# Parasite.net
KiCad netlist of a schematic drawn in EAGLE
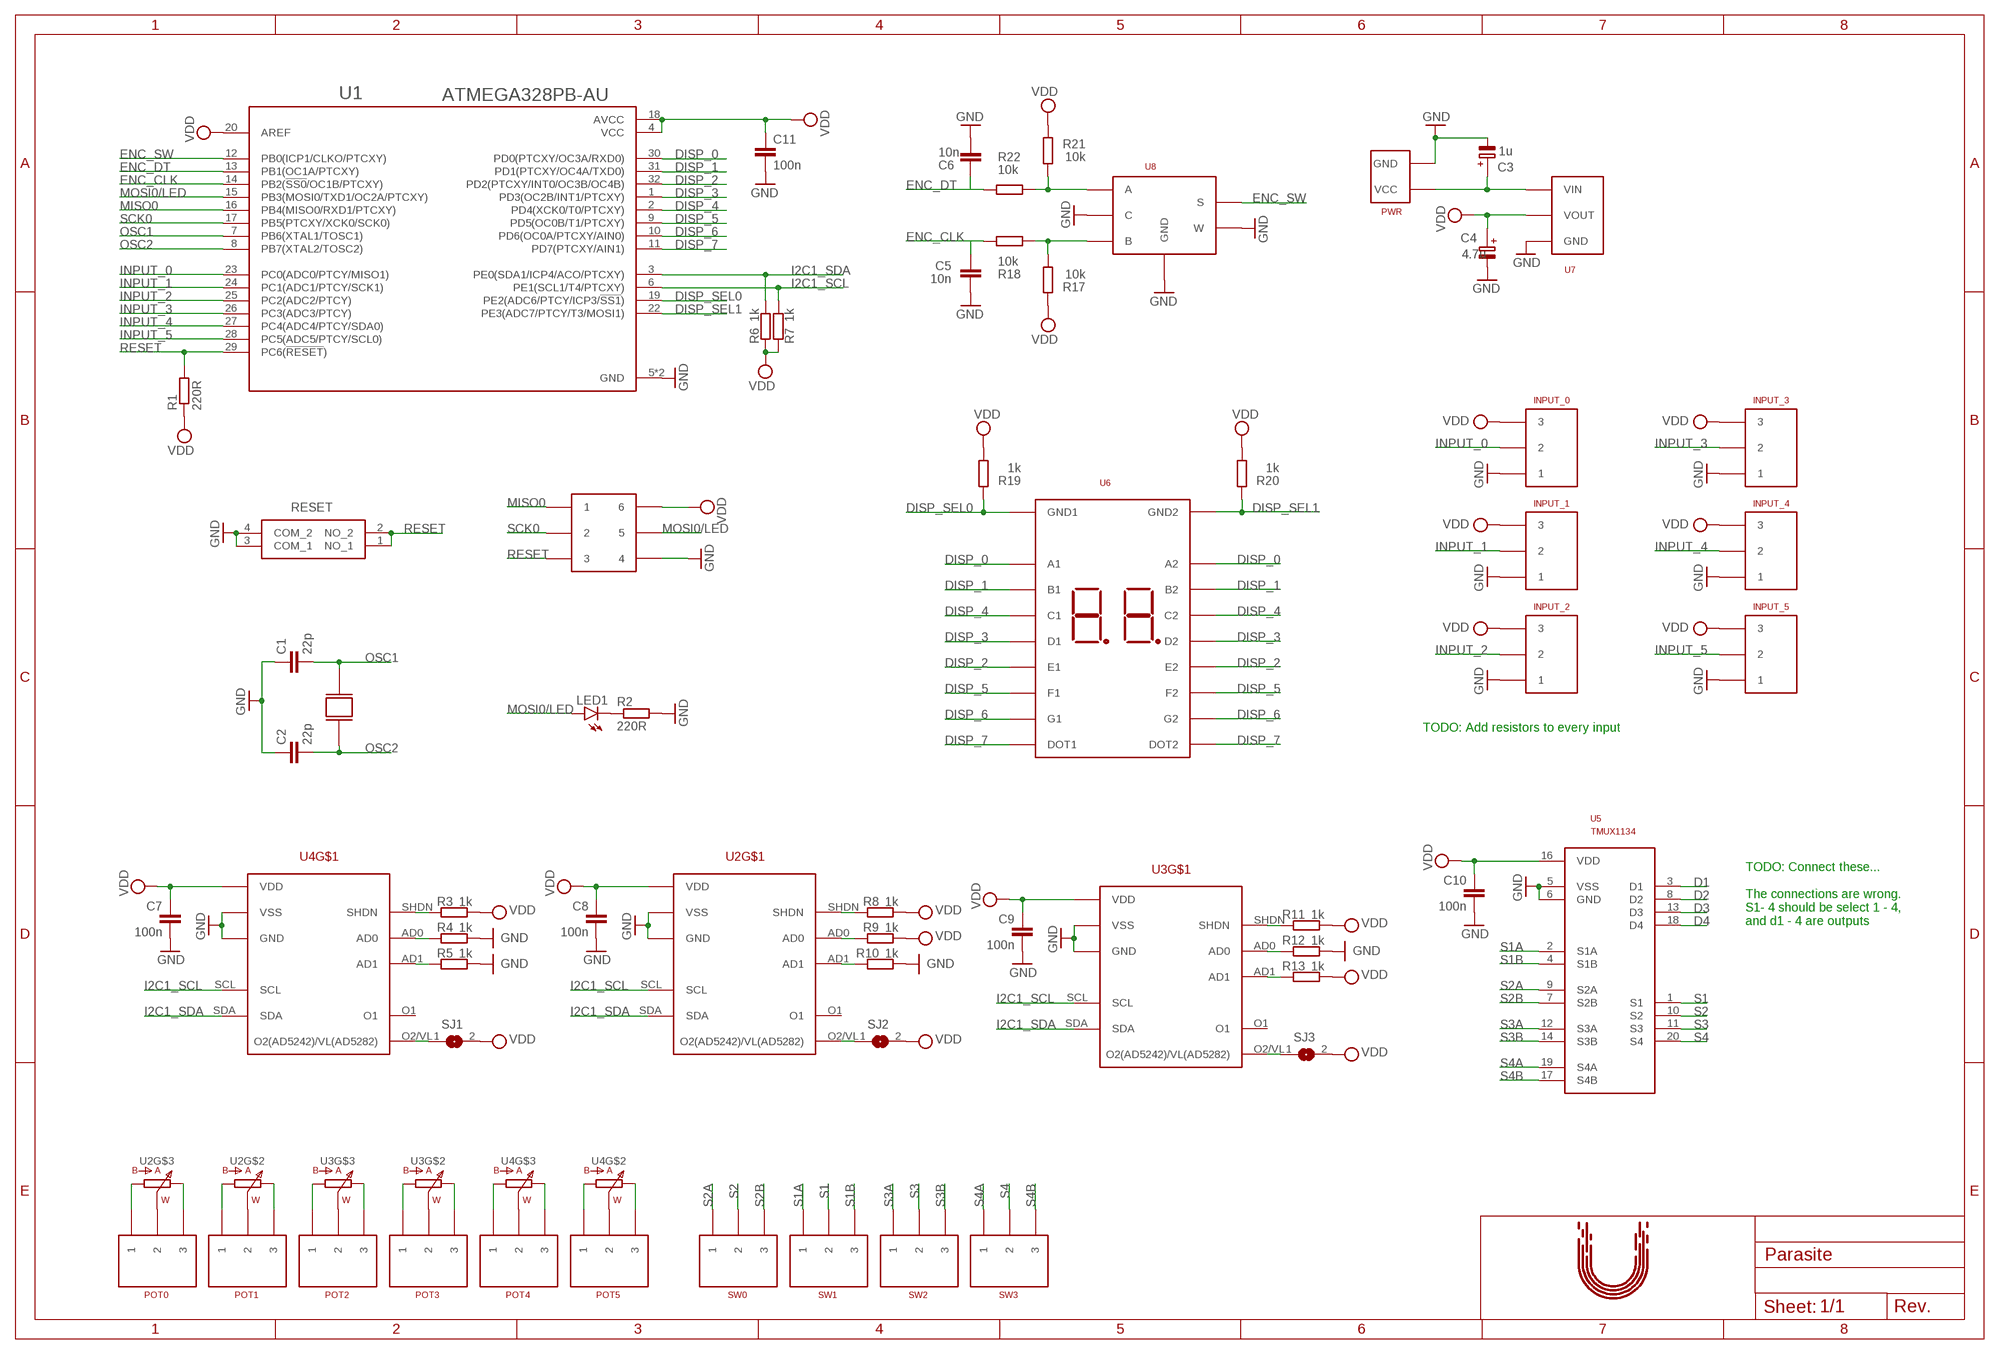
[diagram p0: schematic, sheet 1]

(export (version "E")
  (design (tool "Eeschema 10.0.6"))
  (components
    (comp (ref "C1")
      (value "22p")
      (footprint "eagle-import:C-1206")
      (libsource (lib "eagle-import") (part "CAPACITOR1206"))
    )
    (comp (ref "C2")
      (value "22p")
      (footprint "eagle-import:C-1206")
      (libsource (lib "eagle-import") (part "CAPACITOR1206"))
    )
    (comp (ref "C3")
      (value "1u")
      (footprint "eagle-import:UD-4X5,8_NICHICON")
      (libsource (lib "eagle-import") (part "ELECT_CAPACITORCAP6"))
    )
    (comp (ref "C4")
      (value "4.7u")
      (footprint "eagle-import:UD-4X5,8_NICHICON")
      (libsource (lib "eagle-import") (part "ELECT_CAPACITORCAP6"))
    )
    (comp (ref "C5")
      (value "10n")
      (footprint "eagle-import:C-1206")
      (libsource (lib "eagle-import") (part "CAPACITOR1206"))
    )
    (comp (ref "C6")
      (value "10n")
      (footprint "eagle-import:C-1206")
      (libsource (lib "eagle-import") (part "CAPACITOR1206"))
    )
    (comp (ref "C7")
      (value "100n")
      (footprint "eagle-import:C-1206")
      (libsource (lib "eagle-import") (part "CAPACITOR1206"))
    )
    (comp (ref "C8")
      (value "100n")
      (footprint "eagle-import:C-1206")
      (libsource (lib "eagle-import") (part "CAPACITOR1206"))
    )
    (comp (ref "C9")
      (value "100n")
      (footprint "eagle-import:C-1206")
      (libsource (lib "eagle-import") (part "CAPACITOR1206"))
    )
    (comp (ref "C10")
      (value "100n")
      (footprint "eagle-import:C-1206")
      (libsource (lib "eagle-import") (part "CAPACITOR1206"))
    )
    (comp (ref "C11")
      (value "100n")
      (footprint "eagle-import:C-1206")
      (libsource (lib "eagle-import") (part "CAPACITOR1206"))
    )
    (comp (ref "INPUT_0")
      (value "3_PIN_CONNECTOR")
      (footprint "eagle-import:3_PIN_CONNECTOR")
      (fields (field (name "MPN") " 22-23-2037"))
      (libsource (lib "eagle-import") (part "3_PIN_CONNECTOR"))
    )
    (comp (ref "INPUT_1")
      (value "3_PIN_CONNECTOR")
      (footprint "eagle-import:3_PIN_CONNECTOR")
      (fields (field (name "MPN") " 22-23-2037"))
      (libsource (lib "eagle-import") (part "3_PIN_CONNECTOR"))
    )
    (comp (ref "INPUT_2")
      (value "3_PIN_CONNECTOR")
      (footprint "eagle-import:3_PIN_CONNECTOR")
      (fields (field (name "MPN") " 22-23-2037"))
      (libsource (lib "eagle-import") (part "3_PIN_CONNECTOR"))
    )
    (comp (ref "INPUT_3")
      (value "3_PIN_CONNECTOR")
      (footprint "eagle-import:3_PIN_CONNECTOR")
      (fields (field (name "MPN") " 22-23-2037"))
      (libsource (lib "eagle-import") (part "3_PIN_CONNECTOR"))
    )
    (comp (ref "INPUT_4")
      (value "3_PIN_CONNECTOR")
      (footprint "eagle-import:3_PIN_CONNECTOR")
      (fields (field (name "MPN") " 22-23-2037"))
      (libsource (lib "eagle-import") (part "3_PIN_CONNECTOR"))
    )
    (comp (ref "INPUT_5")
      (value "3_PIN_CONNECTOR")
      (footprint "eagle-import:3_PIN_CONNECTOR")
      (fields (field (name "MPN") " 22-23-2037"))
      (libsource (lib "eagle-import") (part "3_PIN_CONNECTOR"))
    )
    (comp (ref "LED1")
      (value "LEDLED_THROUGH")
      (footprint "eagle-import:LED3MM")
      (libsource (lib "eagle-import") (part "LEDLED_THROUGH"))
    )
    (comp (ref "POT0")
      (value "3_PIN_CONNECTOR")
      (footprint "eagle-import:3_PIN_CONNECTOR")
      (fields (field (name "MPN") " 22-23-2037"))
      (libsource (lib "eagle-import") (part "3_PIN_CONNECTOR"))
    )
    (comp (ref "POT1")
      (value "3_PIN_CONNECTOR")
      (footprint "eagle-import:3_PIN_CONNECTOR")
      (fields (field (name "MPN") " 22-23-2037"))
      (libsource (lib "eagle-import") (part "3_PIN_CONNECTOR"))
    )
    (comp (ref "POT2")
      (value "3_PIN_CONNECTOR")
      (footprint "eagle-import:3_PIN_CONNECTOR")
      (fields (field (name "MPN") " 22-23-2037"))
      (libsource (lib "eagle-import") (part "3_PIN_CONNECTOR"))
    )
    (comp (ref "POT3")
      (value "3_PIN_CONNECTOR")
      (footprint "eagle-import:3_PIN_CONNECTOR")
      (fields (field (name "MPN") " 22-23-2037"))
      (libsource (lib "eagle-import") (part "3_PIN_CONNECTOR"))
    )
    (comp (ref "POT4")
      (value "3_PIN_CONNECTOR")
      (footprint "eagle-import:3_PIN_CONNECTOR")
      (fields (field (name "MPN") " 22-23-2037"))
      (libsource (lib "eagle-import") (part "3_PIN_CONNECTOR"))
    )
    (comp (ref "POT5")
      (value "3_PIN_CONNECTOR")
      (footprint "eagle-import:3_PIN_CONNECTOR")
      (fields (field (name "MPN") " 22-23-2037"))
      (libsource (lib "eagle-import") (part "3_PIN_CONNECTOR"))
    )
    (comp (ref "PWR")
      (value "PWR")
      (footprint "eagle-import:PWR")
      (libsource (lib "eagle-import") (part "PWR"))
    )
    (comp (ref "R1")
      (value "220R")
      (footprint "eagle-import:R1206")
      (libsource (lib "eagle-import") (part "RESISTOR1206"))
    )
    (comp (ref "R2")
      (value "220R")
      (footprint "eagle-import:R1206")
      (libsource (lib "eagle-import") (part "RESISTOR1206"))
    )
    (comp (ref "R3")
      (value "1k")
      (footprint "eagle-import:R1206")
      (libsource (lib "eagle-import") (part "RESISTOR1206"))
    )
    (comp (ref "R4")
      (value "1k")
      (footprint "eagle-import:R1206")
      (libsource (lib "eagle-import") (part "RESISTOR1206"))
    )
    (comp (ref "R5")
      (value "1k")
      (footprint "eagle-import:R1206")
      (libsource (lib "eagle-import") (part "RESISTOR1206"))
    )
    (comp (ref "R6")
      (value "1k")
      (footprint "eagle-import:R1206")
      (libsource (lib "eagle-import") (part "RESISTOR1206"))
    )
    (comp (ref "R7")
      (value "1k")
      (footprint "eagle-import:R1206")
      (libsource (lib "eagle-import") (part "RESISTOR1206"))
    )
    (comp (ref "R8")
      (value "1k")
      (footprint "eagle-import:R1206")
      (libsource (lib "eagle-import") (part "RESISTOR1206"))
    )
    (comp (ref "R9")
      (value "1k")
      (footprint "eagle-import:R1206")
      (libsource (lib "eagle-import") (part "RESISTOR1206"))
    )
    (comp (ref "R10")
      (value "1k")
      (footprint "eagle-import:R1206")
      (libsource (lib "eagle-import") (part "RESISTOR1206"))
    )
    (comp (ref "R11")
      (value "1k")
      (footprint "eagle-import:R1206")
      (libsource (lib "eagle-import") (part "RESISTOR1206"))
    )
    (comp (ref "R12")
      (value "1k")
      (footprint "eagle-import:R1206")
      (libsource (lib "eagle-import") (part "RESISTOR1206"))
    )
    (comp (ref "R13")
      (value "1k")
      (footprint "eagle-import:R1206")
      (libsource (lib "eagle-import") (part "RESISTOR1206"))
    )
    (comp (ref "R17")
      (value "10k")
      (footprint "eagle-import:R1206")
      (libsource (lib "eagle-import") (part "RESISTOR1206"))
    )
    (comp (ref "R18")
      (value "10k")
      (footprint "eagle-import:R1206")
      (libsource (lib "eagle-import") (part "RESISTOR1206"))
    )
    (comp (ref "R19")
      (value "1k")
      (footprint "eagle-import:R1206")
      (libsource (lib "eagle-import") (part "RESISTOR1206"))
    )
    (comp (ref "R20")
      (value "1k")
      (footprint "eagle-import:R1206")
      (libsource (lib "eagle-import") (part "RESISTOR1206"))
    )
    (comp (ref "R21")
      (value "10k")
      (footprint "eagle-import:R1206")
      (libsource (lib "eagle-import") (part "RESISTOR1206"))
    )
    (comp (ref "R22")
      (value "10k")
      (footprint "eagle-import:R1206")
      (libsource (lib "eagle-import") (part "RESISTOR1206"))
    )
    (comp (ref "RESET")
      (value "BUTTON")
      (footprint "eagle-import:PTS647SK38SMTR2LFS")
      (fields (field (name "MPN") "PTS647SK50SMTR2LFS"))
      (libsource (lib "eagle-import") (part "BUTTON"))
    )
    (comp (ref "SJ1")
      (value "JUMPER")
      (footprint "eagle-import:SJ")
      (libsource (lib "eagle-import") (part "JUMPER"))
    )
    (comp (ref "SJ2")
      (value "JUMPER")
      (footprint "eagle-import:SJ")
      (libsource (lib "eagle-import") (part "JUMPER"))
    )
    (comp (ref "SJ3")
      (value "JUMPER")
      (footprint "eagle-import:SJ")
      (libsource (lib "eagle-import") (part "JUMPER"))
    )
    (comp (ref "SW0")
      (value "3_PIN_CONNECTOR")
      (footprint "eagle-import:3_PIN_CONNECTOR")
      (fields (field (name "MPN") " 22-23-2037"))
      (libsource (lib "eagle-import") (part "3_PIN_CONNECTOR"))
    )
    (comp (ref "SW1")
      (value "3_PIN_CONNECTOR")
      (footprint "eagle-import:3_PIN_CONNECTOR")
      (fields (field (name "MPN") " 22-23-2037"))
      (libsource (lib "eagle-import") (part "3_PIN_CONNECTOR"))
    )
    (comp (ref "SW2")
      (value "3_PIN_CONNECTOR")
      (footprint "eagle-import:3_PIN_CONNECTOR")
      (fields (field (name "MPN") " 22-23-2037"))
      (libsource (lib "eagle-import") (part "3_PIN_CONNECTOR"))
    )
    (comp (ref "SW3")
      (value "3_PIN_CONNECTOR")
      (footprint "eagle-import:3_PIN_CONNECTOR")
      (fields (field (name "MPN") " 22-23-2037"))
      (libsource (lib "eagle-import") (part "3_PIN_CONNECTOR"))
    )
    (comp (ref "U$5")
      (value "UTBULT_DESIGN2")
      (footprint "eagle-import:UD_2")
      (libsource (lib "eagle-import") (part "UTBULT_DESIGN2"))
    )
    (comp (ref "U1")
      (value "ATMEGA328PB-AU")
      (footprint "eagle-import:QFP80P900X900X120-32N")
      (libsource (lib "eagle-import") (part "ATMEGA328PB-AU"))
    )
    (comp (ref "U2")
      (value "DIGITAL_POT_AD5242AD5242/AD5282")
      (footprint "eagle-import:SOP65P640X120-16N")
      (fields (field (name "MPN") "AD5242BRUZ1M"))
      (libsource (lib "eagle-import") (part "DIGITAL_POT_AD5242AD5242/AD5282"))
    )
    (comp (ref "U3")
      (value "DIGITAL_POT_AD5282AD5242/AD5282")
      (footprint "eagle-import:SOP65P640X120-16N")
      (fields (field (name "MPN") "AD5282BRUZ50"))
      (libsource (lib "eagle-import") (part "DIGITAL_POT_AD5282AD5242/AD5282"))
    )
    (comp (ref "U4")
      (value "DIGITAL_POT_AD5242AD5242/AD5282")
      (footprint "eagle-import:SOP65P640X120-16N")
      (fields (field (name "MPN") "AD5242BRUZ1M"))
      (libsource (lib "eagle-import") (part "DIGITAL_POT_AD5242AD5242/AD5282"))
    )
    (comp (ref "U5")
      (value "TMUX1134")
      (footprint "eagle-import:SOP65P640X120-20N")
      (fields (field (name "MPN") "TMUX1134PWR "))
      (libsource (lib "eagle-import") (part "TMUX1134"))
    )
    (comp (ref "U6")
      (value "7_SEGMENT_DISPLAY")
      (footprint "eagle-import:7_SEGMENT_DISPLAY")
      (fields (field (name "MPN") "LB-602MA2"))
      (libsource (lib "eagle-import") (part "7_SEGMENT_DISPLAY"))
    )
    (comp (ref "U7")
      (value "VOLTAGE_REGULATOR_LDL1117S50RVOLTAGE_REGULATOR_LDL1117S50R")
      (footprint "eagle-import:SOT230P700X180-4N")
      (fields (field (name "MPN") "LDL1117S50R"))
      (libsource (lib "eagle-import") (part "VOLTAGE_REGULATOR_LDL1117S50RVOLTAGE_REGULATOR_LDL1117S50R"))
    )
    (comp (ref "U8")
      (value "ROTARY_ENCODER")
      (footprint "eagle-import:ENCODER_PEC11H-4220F")
      (fields (field (name "MPN") "PEC11H-4220F-S0024"))
      (libsource (lib "eagle-import") (part "ROTARY_ENCODER"))
    )
    (comp (ref "U9")
      (value "3X2_PINHEADER3X2_PINHEADER")
      (footprint "eagle-import:HDRV6W64P254_2X3_900X508X838B")
      (fields (field (name "MPN") "5-146258-3"))
      (libsource (lib "eagle-import") (part "3X2_PINHEADER3X2_PINHEADER"))
    )
    (comp (ref "U10")
      (value "CRYSTAL_LFXTAL027946BULKCRYSTAL_LFXTAL027946BULK")
      (footprint "eagle-import:XTAL1140X490X430N")
      (fields (field (name "MPN") "LFXTAL027946Bulk"))
      (libsource (lib "eagle-import") (part "CRYSTAL_LFXTAL027946BULKCRYSTAL_LFXTAL027946BULK"))
    )
  )
  (nets
    (net (code "1") (name "/D1") (class "Default")
      (node (ref "U5") (pin "3") (pinfunction "D1_3") (pintype "bidirectional"))
    )
    (net (code "2") (name "/D2") (class "Default")
      (node (ref "U5") (pin "8") (pinfunction "D2_8") (pintype "bidirectional"))
    )
    (net (code "3") (name "/D3") (class "Default")
      (node (ref "U5") (pin "13") (pinfunction "D3_13") (pintype "bidirectional"))
    )
    (net (code "4") (name "/D4") (class "Default")
      (node (ref "U5") (pin "18") (pinfunction "D4_18") (pintype "bidirectional"))
    )
    (net (code "5") (name "/DISP_0") (class "Default")
      (node (ref "U1") (pin "30") (pinfunction "PD0(PTCXY/OC3A/RXD0)_30") (pintype "bidirectional"))
      (node (ref "U6") (pin "A1") (pinfunction "A1_A1") (pintype "input"))
      (node (ref "U6") (pin "A2") (pinfunction "A2_A2") (pintype "input"))
    )
    (net (code "6") (name "/DISP_1") (class "Default")
      (node (ref "U1") (pin "31") (pinfunction "PD1(PTCXY/OC4A/TXD0)_31") (pintype "bidirectional"))
      (node (ref "U6") (pin "B1") (pinfunction "B1_B1") (pintype "input"))
      (node (ref "U6") (pin "B2") (pinfunction "B2_B2") (pintype "input"))
    )
    (net (code "7") (name "/DISP_2") (class "Default")
      (node (ref "U1") (pin "32") (pinfunction "PD2(PTCXY/INT0/OC3B/OC4B)_32") (pintype "bidirectional"))
      (node (ref "U6") (pin "E1") (pinfunction "E1_E1") (pintype "input"))
      (node (ref "U6") (pin "E2") (pinfunction "E2_E2") (pintype "input"))
    )
    (net (code "8") (name "/DISP_3") (class "Default")
      (node (ref "U1") (pin "1") (pinfunction "PD3(OC2B/INT1/PTCXY)_1") (pintype "bidirectional"))
      (node (ref "U6") (pin "D1") (pinfunction "D1_D1") (pintype "input"))
      (node (ref "U6") (pin "D2") (pinfunction "D2_D2") (pintype "input"))
    )
    (net (code "9") (name "/DISP_4") (class "Default")
      (node (ref "U1") (pin "2") (pinfunction "PD4(XCK0/T0/PTCXY)_2") (pintype "bidirectional"))
      (node (ref "U6") (pin "C1") (pinfunction "C1_C1") (pintype "input"))
      (node (ref "U6") (pin "C2") (pinfunction "C2_C2") (pintype "input"))
    )
    (net (code "10") (name "/DISP_5") (class "Default")
      (node (ref "U1") (pin "9") (pinfunction "PD5(OC0B/T1/PTCXY)_9") (pintype "bidirectional"))
      (node (ref "U6") (pin "F1") (pinfunction "F1_F1") (pintype "input"))
      (node (ref "U6") (pin "F2") (pinfunction "F2_F2") (pintype "input"))
    )
    (net (code "11") (name "/DISP_6") (class "Default")
      (node (ref "U1") (pin "10") (pinfunction "PD6(OC0A/PTCXY/AIN0)_10") (pintype "bidirectional"))
      (node (ref "U6") (pin "G1") (pinfunction "G1_G1") (pintype "input"))
      (node (ref "U6") (pin "G2") (pinfunction "G2_G2") (pintype "input"))
    )
    (net (code "12") (name "/DISP_7") (class "Default")
      (node (ref "U1") (pin "11") (pinfunction "PD7(PTCXY/AIN1)_11") (pintype "bidirectional"))
      (node (ref "U6") (pin "DOT1") (pinfunction "DOT1_DOT1") (pintype "input"))
      (node (ref "U6") (pin "DOT2") (pinfunction "DOT2_DOT2") (pintype "input"))
    )
    (net (code "13") (name "/DISP_SEL0") (class "Default")
      (node (ref "R19") (pin "1") (pinfunction "1_1") (pintype "passive"))
      (node (ref "U1") (pin "19") (pinfunction "PE2(ADC6/PTCY/ICP3/~{SS1})_19") (pintype "bidirectional"))
      (node (ref "U6") (pin "GND1") (pinfunction "GND1_GND1") (pintype "output"))
    )
    (net (code "14") (name "/DISP_SEL1") (class "Default")
      (node (ref "R20") (pin "1") (pinfunction "1_1") (pintype "passive"))
      (node (ref "U1") (pin "22") (pinfunction "PE3(ADC7/PTCY/T3/MOSI1)_22") (pintype "bidirectional"))
      (node (ref "U6") (pin "GND2") (pinfunction "GND2_GND2") (pintype "output"))
    )
    (net (code "15") (name "/ENC_CLK") (class "Default")
      (node (ref "C5") (pin "P$2") (pinfunction "2_P$2") (pintype "passive"))
      (node (ref "R18") (pin "2") (pinfunction "2_2") (pintype "passive"))
      (node (ref "U1") (pin "14") (pinfunction "PB2(~{SS0}/OC1B/PTCXY)_14") (pintype "bidirectional"))
    )
    (net (code "16") (name "/ENC_DT") (class "Default")
      (node (ref "C6") (pin "P$2") (pinfunction "2_P$2") (pintype "passive"))
      (node (ref "R22") (pin "2") (pinfunction "2_2") (pintype "passive"))
      (node (ref "U1") (pin "13") (pinfunction "PB1(OC1A/PTCXY)_13") (pintype "bidirectional"))
    )
    (net (code "17") (name "/ENC_SW") (class "Default")
      (node (ref "U1") (pin "12") (pinfunction "PB0(ICP1/CLKO/PTCXY)_12") (pintype "bidirectional"))
      (node (ref "U8") (pin "S") (pinfunction "S_S") (pintype "bidirectional"))
    )
    (net (code "18") (name "/I2C1_SCL") (class "Default")
      (node (ref "R7") (pin "1") (pinfunction "1_1") (pintype "passive"))
      (node (ref "U1") (pin "6") (pinfunction "PE1(SCL1/T4/PTCXY)_6") (pintype "bidirectional"))
      (node (ref "U2") (pin "SCL") (pinfunction "SCL_SCL") (pintype "input"))
      (node (ref "U3") (pin "SCL") (pinfunction "SCL_SCL") (pintype "input"))
      (node (ref "U4") (pin "SCL") (pinfunction "SCL_SCL") (pintype "input"))
    )
    (net (code "19") (name "/I2C1_SDA") (class "Default")
      (node (ref "R6") (pin "1") (pinfunction "1_1") (pintype "passive"))
      (node (ref "U1") (pin "3") (pinfunction "PE0(SDA1/ICP4/ACO/PTCXY)_3") (pintype "bidirectional"))
      (node (ref "U2") (pin "SDA") (pinfunction "SDA_SDA") (pintype "bidirectional"))
      (node (ref "U3") (pin "SDA") (pinfunction "SDA_SDA") (pintype "bidirectional"))
      (node (ref "U4") (pin "SDA") (pinfunction "SDA_SDA") (pintype "bidirectional"))
    )
    (net (code "20") (name "/INPUT_0") (class "Default")
      (node (ref "INPUT_0") (pin "P$2") (pinfunction "2_P$2") (pintype "bidirectional"))
      (node (ref "U1") (pin "23") (pinfunction "PC0(ADC0/PTCY/MISO1)_23") (pintype "bidirectional"))
    )
    (net (code "21") (name "/INPUT_1") (class "Default")
      (node (ref "INPUT_1") (pin "P$2") (pinfunction "2_P$2") (pintype "bidirectional"))
      (node (ref "U1") (pin "24") (pinfunction "PC1(ADC1/PTCY/SCK1)_24") (pintype "bidirectional"))
    )
    (net (code "22") (name "/INPUT_2") (class "Default")
      (node (ref "INPUT_2") (pin "P$2") (pinfunction "2_P$2") (pintype "bidirectional"))
      (node (ref "U1") (pin "25") (pinfunction "PC2(ADC2/PTCY)_25") (pintype "bidirectional"))
    )
    (net (code "23") (name "/INPUT_3") (class "Default")
      (node (ref "INPUT_3") (pin "P$2") (pinfunction "2_P$2") (pintype "bidirectional"))
      (node (ref "U1") (pin "26") (pinfunction "PC3(ADC3/PTCY)_26") (pintype "bidirectional"))
    )
    (net (code "24") (name "/INPUT_4") (class "Default")
      (node (ref "INPUT_4") (pin "P$2") (pinfunction "2_P$2") (pintype "bidirectional"))
      (node (ref "U1") (pin "27") (pinfunction "PC4(ADC4/PTCY/SDA0)_27") (pintype "bidirectional"))
    )
    (net (code "25") (name "/INPUT_5") (class "Default")
      (node (ref "INPUT_5") (pin "P$2") (pinfunction "2_P$2") (pintype "bidirectional"))
      (node (ref "U1") (pin "28") (pinfunction "PC5(ADC5/PTCY/SCL0)_28") (pintype "bidirectional"))
    )
    (net (code "26") (name "/MISO0") (class "Default")
      (node (ref "U1") (pin "16") (pinfunction "PB4(MISO0/RXD1/PTCXY)_16") (pintype "bidirectional"))
      (node (ref "U9") (pin "1") (pinfunction "1_1") (pintype "bidirectional"))
    )
    (net (code "27") (name "/MOSI0{slash}LED") (class "Default")
      (node (ref "LED1") (pin "A") (pinfunction "A_A") (pintype "passive"))
      (node (ref "U1") (pin "15") (pinfunction "PB3(MOSI0/TXD1/OC2A/PTCXY)_15") (pintype "bidirectional"))
      (node (ref "U9") (pin "5") (pinfunction "5_5") (pintype "bidirectional"))
    )
    (net (code "28") (name "/OSC1") (class "Default")
      (node (ref "C1") (pin "P$2") (pinfunction "2_P$2") (pintype "passive"))
      (node (ref "U1") (pin "7") (pinfunction "PB6(XTAL1/TOSC1)_7") (pintype "bidirectional"))
      (node (ref "U10") (pin "2") (pinfunction "P$2_2") (pintype "bidirectional"))
    )
    (net (code "29") (name "/OSC2") (class "Default")
      (node (ref "C2") (pin "P$2") (pinfunction "2_P$2") (pintype "passive"))
      (node (ref "U1") (pin "8") (pinfunction "PB7(XTAL2/TOSC2)_8") (pintype "bidirectional"))
      (node (ref "U10") (pin "1") (pinfunction "P$1_1") (pintype "bidirectional"))
    )
    (net (code "30") (name "/RESET") (class "Default")
      (node (ref "R1") (pin "2") (pinfunction "2_2") (pintype "passive"))
      (node (ref "RESET") (pin "1") (pinfunction "NO_1_1") (pintype "bidirectional"))
      (node (ref "RESET") (pin "2") (pinfunction "NO_2_2") (pintype "bidirectional"))
      (node (ref "U1") (pin "29") (pinfunction "PC6(~{RESET})_29") (pintype "bidirectional"))
      (node (ref "U9") (pin "3") (pinfunction "3_3") (pintype "bidirectional"))
    )
    (net (code "31") (name "/S1") (class "Default")
      (node (ref "SW1") (pin "P$2") (pinfunction "2_P$2") (pintype "bidirectional"))
      (node (ref "U5") (pin "1") (pinfunction "S1_1") (pintype "bidirectional"))
    )
    (net (code "32") (name "/S1A") (class "Default")
      (node (ref "SW1") (pin "P$1") (pinfunction "1_P$1") (pintype "bidirectional"))
      (node (ref "U5") (pin "2") (pinfunction "S1A_2") (pintype "bidirectional"))
    )
    (net (code "33") (name "/S1B") (class "Default")
      (node (ref "SW1") (pin "P$3") (pinfunction "3_P$3") (pintype "bidirectional"))
      (node (ref "U5") (pin "4") (pinfunction "S1B_4") (pintype "bidirectional"))
    )
    (net (code "34") (name "/S2") (class "Default")
      (node (ref "SW0") (pin "P$2") (pinfunction "2_P$2") (pintype "bidirectional"))
      (node (ref "U5") (pin "10") (pinfunction "S2_10") (pintype "bidirectional"))
    )
    (net (code "35") (name "/S2A") (class "Default")
      (node (ref "SW0") (pin "P$1") (pinfunction "1_P$1") (pintype "bidirectional"))
      (node (ref "U5") (pin "9") (pinfunction "S2A_9") (pintype "bidirectional"))
    )
    (net (code "36") (name "/S2B") (class "Default")
      (node (ref "SW0") (pin "P$3") (pinfunction "3_P$3") (pintype "bidirectional"))
      (node (ref "U5") (pin "7") (pinfunction "S2B_7") (pintype "bidirectional"))
    )
    (net (code "37") (name "/S3") (class "Default")
      (node (ref "SW2") (pin "P$2") (pinfunction "2_P$2") (pintype "bidirectional"))
      (node (ref "U5") (pin "11") (pinfunction "S3_11") (pintype "bidirectional"))
    )
    (net (code "38") (name "/S3A") (class "Default")
      (node (ref "SW2") (pin "P$1") (pinfunction "1_P$1") (pintype "bidirectional"))
      (node (ref "U5") (pin "12") (pinfunction "S3A_12") (pintype "bidirectional"))
    )
    (net (code "39") (name "/S3B") (class "Default")
      (node (ref "SW2") (pin "P$3") (pinfunction "3_P$3") (pintype "bidirectional"))
      (node (ref "U5") (pin "14") (pinfunction "S3B_14") (pintype "bidirectional"))
    )
    (net (code "40") (name "/S4") (class "Default")
      (node (ref "SW3") (pin "P$2") (pinfunction "2_P$2") (pintype "bidirectional"))
      (node (ref "U5") (pin "20") (pinfunction "S4_20") (pintype "bidirectional"))
    )
    (net (code "41") (name "/S4A") (class "Default")
      (node (ref "SW3") (pin "P$1") (pinfunction "1_P$1") (pintype "bidirectional"))
      (node (ref "U5") (pin "19") (pinfunction "S4A_19") (pintype "bidirectional"))
    )
    (net (code "42") (name "/S4B") (class "Default")
      (node (ref "SW3") (pin "P$3") (pinfunction "3_P$3") (pintype "bidirectional"))
      (node (ref "U5") (pin "17") (pinfunction "S4B_17") (pintype "bidirectional"))
    )
    (net (code "43") (name "/SCK0") (class "Default")
      (node (ref "U1") (pin "17") (pinfunction "PB5(PTCXY/XCK0/SCK0)_17") (pintype "bidirectional"))
      (node (ref "U9") (pin "2") (pinfunction "2_2") (pintype "bidirectional"))
    )
    (net (code "44") (name "GND") (class "Default")
      (node (ref "C1") (pin "P$1") (pinfunction "1_P$1") (pintype "passive"))
      (node (ref "C10") (pin "P$2") (pinfunction "2_P$2") (pintype "passive"))
      (node (ref "C11") (pin "P$2") (pinfunction "2_P$2") (pintype "passive"))
      (node (ref "C2") (pin "P$1") (pinfunction "1_P$1") (pintype "passive"))
      (node (ref "C3") (pin "-") (pinfunction "-_-") (pintype "passive"))
      (node (ref "C4") (pin "-") (pinfunction "-_-") (pintype "passive"))
      (node (ref "C5") (pin "P$1") (pinfunction "1_P$1") (pintype "passive"))
      (node (ref "C6") (pin "P$1") (pinfunction "1_P$1") (pintype "passive"))
      (node (ref "C7") (pin "P$2") (pinfunction "2_P$2") (pintype "passive"))
      (node (ref "C8") (pin "P$2") (pinfunction "2_P$2") (pintype "passive"))
      (node (ref "C9") (pin "P$2") (pinfunction "2_P$2") (pintype "passive"))
      (node (ref "INPUT_0") (pin "P$1") (pinfunction "1_P$1") (pintype "bidirectional"))
      (node (ref "INPUT_1") (pin "P$1") (pinfunction "1_P$1") (pintype "bidirectional"))
      (node (ref "INPUT_2") (pin "P$1") (pinfunction "1_P$1") (pintype "bidirectional"))
      (node (ref "INPUT_3") (pin "P$1") (pinfunction "1_P$1") (pintype "bidirectional"))
      (node (ref "INPUT_4") (pin "P$1") (pinfunction "1_P$1") (pintype "bidirectional"))
      (node (ref "INPUT_5") (pin "P$1") (pinfunction "1_P$1") (pintype "bidirectional"))
      (node (ref "PWR") (pin "P$2") (pinfunction "GND_P$2") (pintype "bidirectional"))
      (node (ref "R10") (pin "1") (pinfunction "1_1") (pintype "passive"))
      (node (ref "R12") (pin "1") (pinfunction "1_1") (pintype "passive"))
      (node (ref "R2") (pin "2") (pinfunction "2_2") (pintype "passive"))
      (node (ref "R4") (pin "1") (pinfunction "1_1") (pintype "passive"))
      (node (ref "R5") (pin "1") (pinfunction "1_1") (pintype "passive"))
      (node (ref "RESET") (pin "3") (pinfunction "COM_1_3") (pintype "bidirectional"))
      (node (ref "RESET") (pin "4") (pinfunction "COM_2_4") (pintype "bidirectional"))
      (node (ref "U1") (pin "21") (pinfunction "GND_21") (pintype "power_in"))
      (node (ref "U1") (pin "5") (pinfunction "GND_5") (pintype "power_in"))
      (node (ref "U2") (pin "GND") (pinfunction "GND_GND") (pintype "power_in"))
      (node (ref "U2") (pin "VSS") (pinfunction "VSS_VSS") (pintype "power_in"))
      (node (ref "U3") (pin "GND") (pinfunction "GND_GND") (pintype "power_in"))
      (node (ref "U3") (pin "VSS") (pinfunction "VSS_VSS") (pintype "power_in"))
      (node (ref "U4") (pin "GND") (pinfunction "GND_GND") (pintype "power_in"))
      (node (ref "U4") (pin "VSS") (pinfunction "VSS_VSS") (pintype "power_in"))
      (node (ref "U5") (pin "5") (pinfunction "VSS_5") (pintype "bidirectional"))
      (node (ref "U5") (pin "6") (pinfunction "GND_6") (pintype "bidirectional"))
      (node (ref "U7") (pin "1") (pinfunction "GND_1") (pintype "power_in"))
      (node (ref "U8") (pin "C") (pinfunction "C_C") (pintype "output"))
      (node (ref "U8") (pin "GND1") (pinfunction "GND_GND1") (pintype "power_in"))
      (node (ref "U8") (pin "GND2") (pinfunction "GND_GND2") (pintype "power_in"))
      (node (ref "U8") (pin "W") (pinfunction "W_W") (pintype "bidirectional"))
      (node (ref "U9") (pin "4") (pinfunction "4_4") (pintype "bidirectional"))
    )
    (net (code "45") (name "Net-(LED1-C)") (class "Default")
      (node (ref "LED1") (pin "K") (pinfunction "C_K") (pintype "passive"))
      (node (ref "R2") (pin "1") (pinfunction "1_1") (pintype "passive"))
    )
    (net (code "46") (name "Net-(POT0-1)") (class "Default")
      (node (ref "POT0") (pin "P$1") (pinfunction "1_P$1") (pintype "bidirectional"))
      (node (ref "U2") (pin "B2") (pinfunction "B_B2") (pintype "passive"))
    )
    (net (code "47") (name "Net-(POT0-2)") (class "Default")
      (node (ref "POT0") (pin "P$2") (pinfunction "2_P$2") (pintype "bidirectional"))
      (node (ref "U2") (pin "W2") (pinfunction "W_W2") (pintype "passive"))
    )
    (net (code "48") (name "Net-(POT0-3)") (class "Default")
      (node (ref "POT0") (pin "P$3") (pinfunction "3_P$3") (pintype "bidirectional"))
      (node (ref "U2") (pin "A2") (pinfunction "A_A2") (pintype "passive"))
    )
    (net (code "49") (name "Net-(POT1-1)") (class "Default")
      (node (ref "POT1") (pin "P$1") (pinfunction "1_P$1") (pintype "bidirectional"))
      (node (ref "U2") (pin "B1") (pinfunction "B_B1") (pintype "passive"))
    )
    (net (code "50") (name "Net-(POT1-2)") (class "Default")
      (node (ref "POT1") (pin "P$2") (pinfunction "2_P$2") (pintype "bidirectional"))
      (node (ref "U2") (pin "W1") (pinfunction "W_W1") (pintype "passive"))
    )
    (net (code "51") (name "Net-(POT1-3)") (class "Default")
      (node (ref "POT1") (pin "P$3") (pinfunction "3_P$3") (pintype "bidirectional"))
      (node (ref "U2") (pin "A1") (pinfunction "A_A1") (pintype "passive"))
    )
    (net (code "52") (name "Net-(POT2-1)") (class "Default")
      (node (ref "POT2") (pin "P$1") (pinfunction "1_P$1") (pintype "bidirectional"))
      (node (ref "U3") (pin "B2") (pinfunction "B_B2") (pintype "passive"))
    )
    (net (code "53") (name "Net-(POT2-2)") (class "Default")
      (node (ref "POT2") (pin "P$2") (pinfunction "2_P$2") (pintype "bidirectional"))
      (node (ref "U3") (pin "W2") (pinfunction "W_W2") (pintype "passive"))
    )
    (net (code "54") (name "Net-(POT2-3)") (class "Default")
      (node (ref "POT2") (pin "P$3") (pinfunction "3_P$3") (pintype "bidirectional"))
      (node (ref "U3") (pin "A2") (pinfunction "A_A2") (pintype "passive"))
    )
    (net (code "55") (name "Net-(POT3-1)") (class "Default")
      (node (ref "POT3") (pin "P$1") (pinfunction "1_P$1") (pintype "bidirectional"))
      (node (ref "U3") (pin "B1") (pinfunction "B_B1") (pintype "passive"))
    )
    (net (code "56") (name "Net-(POT3-2)") (class "Default")
      (node (ref "POT3") (pin "P$2") (pinfunction "2_P$2") (pintype "bidirectional"))
      (node (ref "U3") (pin "W1") (pinfunction "W_W1") (pintype "passive"))
    )
    (net (code "57") (name "Net-(POT3-3)") (class "Default")
      (node (ref "POT3") (pin "P$3") (pinfunction "3_P$3") (pintype "bidirectional"))
      (node (ref "U3") (pin "A1") (pinfunction "A_A1") (pintype "passive"))
    )
    (net (code "58") (name "Net-(POT4-1)") (class "Default")
      (node (ref "POT4") (pin "P$1") (pinfunction "1_P$1") (pintype "bidirectional"))
      (node (ref "U4") (pin "B2") (pinfunction "B_B2") (pintype "passive"))
    )
    (net (code "59") (name "Net-(POT4-2)") (class "Default")
      (node (ref "POT4") (pin "P$2") (pinfunction "2_P$2") (pintype "bidirectional"))
      (node (ref "U4") (pin "W2") (pinfunction "W_W2") (pintype "passive"))
    )
    (net (code "60") (name "Net-(POT4-3)") (class "Default")
      (node (ref "POT4") (pin "P$3") (pinfunction "3_P$3") (pintype "bidirectional"))
      (node (ref "U4") (pin "A2") (pinfunction "A_A2") (pintype "passive"))
    )
    (net (code "61") (name "Net-(POT5-1)") (class "Default")
      (node (ref "POT5") (pin "P$1") (pinfunction "1_P$1") (pintype "bidirectional"))
      (node (ref "U4") (pin "B1") (pinfunction "B_B1") (pintype "passive"))
    )
    (net (code "62") (name "Net-(POT5-2)") (class "Default")
      (node (ref "POT5") (pin "P$2") (pinfunction "2_P$2") (pintype "bidirectional"))
      (node (ref "U4") (pin "W1") (pinfunction "W_W1") (pintype "passive"))
    )
    (net (code "63") (name "Net-(POT5-3)") (class "Default")
      (node (ref "POT5") (pin "P$3") (pinfunction "3_P$3") (pintype "bidirectional"))
      (node (ref "U4") (pin "A1") (pinfunction "A_A1") (pintype "passive"))
    )
    (net (code "64") (name "Net-(PWR-VCC)") (class "Default")
      (node (ref "C3") (pin "+") (pinfunction "+_+") (pintype "passive"))
      (node (ref "PWR") (pin "P$1") (pinfunction "VCC_P$1") (pintype "bidirectional"))
      (node (ref "U7") (pin "3") (pinfunction "VIN_3") (pintype "power_in"))
    )
    (net (code "65") (name "Net-(R3-Pad2)") (class "Default")
      (node (ref "R3") (pin "2") (pinfunction "2_2") (pintype "passive"))
      (node (ref "U4") (pin "SHDN") (pinfunction "SHDN_SHDN") (pintype "input"))
    )
    (net (code "66") (name "Net-(R4-Pad2)") (class "Default")
      (node (ref "R4") (pin "2") (pinfunction "2_2") (pintype "passive"))
      (node (ref "U4") (pin "AD0") (pinfunction "AD0_AD0") (pintype "input"))
    )
    (net (code "67") (name "Net-(R5-Pad2)") (class "Default")
      (node (ref "R5") (pin "2") (pinfunction "2_2") (pintype "passive"))
      (node (ref "U4") (pin "AD1") (pinfunction "AD1_AD1") (pintype "input"))
    )
    (net (code "68") (name "Net-(R8-Pad2)") (class "Default")
      (node (ref "R8") (pin "2") (pinfunction "2_2") (pintype "passive"))
      (node (ref "U2") (pin "SHDN") (pinfunction "SHDN_SHDN") (pintype "input"))
    )
    (net (code "69") (name "Net-(R9-Pad2)") (class "Default")
      (node (ref "R9") (pin "2") (pinfunction "2_2") (pintype "passive"))
      (node (ref "U2") (pin "AD0") (pinfunction "AD0_AD0") (pintype "input"))
    )
    (net (code "70") (name "Net-(R10-Pad2)") (class "Default")
      (node (ref "R10") (pin "2") (pinfunction "2_2") (pintype "passive"))
      (node (ref "U2") (pin "AD1") (pinfunction "AD1_AD1") (pintype "input"))
    )
    (net (code "71") (name "Net-(R11-Pad2)") (class "Default")
      (node (ref "R11") (pin "2") (pinfunction "2_2") (pintype "passive"))
      (node (ref "U3") (pin "SHDN") (pinfunction "SHDN_SHDN") (pintype "input"))
    )
    (net (code "72") (name "Net-(R12-Pad2)") (class "Default")
      (node (ref "R12") (pin "2") (pinfunction "2_2") (pintype "passive"))
      (node (ref "U3") (pin "AD0") (pinfunction "AD0_AD0") (pintype "input"))
    )
    (net (code "73") (name "Net-(R13-Pad2)") (class "Default")
      (node (ref "R13") (pin "2") (pinfunction "2_2") (pintype "passive"))
      (node (ref "U3") (pin "AD1") (pinfunction "AD1_AD1") (pintype "input"))
    )
    (net (code "74") (name "Net-(R17-Pad2)") (class "Default")
      (node (ref "R17") (pin "2") (pinfunction "2_2") (pintype "passive"))
      (node (ref "R18") (pin "1") (pinfunction "1_1") (pintype "passive"))
      (node (ref "U8") (pin "B") (pinfunction "B_B") (pintype "input"))
    )
    (net (code "75") (name "Net-(R21-Pad2)") (class "Default")
      (node (ref "R21") (pin "2") (pinfunction "2_2") (pintype "passive"))
      (node (ref "R22") (pin "1") (pinfunction "1_1") (pintype "passive"))
      (node (ref "U8") (pin "A") (pinfunction "A_A") (pintype "input"))
    )
    (net (code "76") (name "Net-(U2A-O2(AD5242){slash}VL(AD5282))") (class "Default")
      (node (ref "SJ2") (pin "1") (pinfunction "1_1") (pintype "passive"))
      (node (ref "U2") (pin "O2/VL") (pinfunction "O2(AD5242)/VL(AD5282)_O2/VL") (pintype "bidirectional"))
    )
    (net (code "77") (name "Net-(U3A-O2(AD5242){slash}VL(AD5282))") (class "Default")
      (node (ref "SJ3") (pin "1") (pinfunction "1_1") (pintype "passive"))
      (node (ref "U3") (pin "O2/VL") (pinfunction "O2(AD5242)/VL(AD5282)_O2/VL") (pintype "bidirectional"))
    )
    (net (code "78") (name "Net-(U4A-O2(AD5242){slash}VL(AD5282))") (class "Default")
      (node (ref "SJ1") (pin "1") (pinfunction "1_1") (pintype "passive"))
      (node (ref "U4") (pin "O2/VL") (pinfunction "O2(AD5242)/VL(AD5282)_O2/VL") (pintype "bidirectional"))
    )
    (net (code "79") (name "VDD") (class "Default")
      (node (ref "C10") (pin "P$1") (pinfunction "1_P$1") (pintype "passive"))
      (node (ref "C11") (pin "P$1") (pinfunction "1_P$1") (pintype "passive"))
      (node (ref "C4") (pin "+") (pinfunction "+_+") (pintype "passive"))
      (node (ref "C7") (pin "P$1") (pinfunction "1_P$1") (pintype "passive"))
      (node (ref "C8") (pin "P$1") (pinfunction "1_P$1") (pintype "passive"))
      (node (ref "C9") (pin "P$1") (pinfunction "1_P$1") (pintype "passive"))
      (node (ref "INPUT_0") (pin "P$3") (pinfunction "3_P$3") (pintype "bidirectional"))
      (node (ref "INPUT_1") (pin "P$3") (pinfunction "3_P$3") (pintype "bidirectional"))
      (node (ref "INPUT_2") (pin "P$3") (pinfunction "3_P$3") (pintype "bidirectional"))
      (node (ref "INPUT_3") (pin "P$3") (pinfunction "3_P$3") (pintype "bidirectional"))
      (node (ref "INPUT_4") (pin "P$3") (pinfunction "3_P$3") (pintype "bidirectional"))
      (node (ref "INPUT_5") (pin "P$3") (pinfunction "3_P$3") (pintype "bidirectional"))
      (node (ref "R1") (pin "1") (pinfunction "1_1") (pintype "passive"))
      (node (ref "R11") (pin "1") (pinfunction "1_1") (pintype "passive"))
      (node (ref "R13") (pin "1") (pinfunction "1_1") (pintype "passive"))
      (node (ref "R17") (pin "1") (pinfunction "1_1") (pintype "passive"))
      (node (ref "R19") (pin "2") (pinfunction "2_2") (pintype "passive"))
      (node (ref "R20") (pin "2") (pinfunction "2_2") (pintype "passive"))
      (node (ref "R21") (pin "1") (pinfunction "1_1") (pintype "passive"))
      (node (ref "R3") (pin "1") (pinfunction "1_1") (pintype "passive"))
      (node (ref "R6") (pin "2") (pinfunction "2_2") (pintype "passive"))
      (node (ref "R7") (pin "2") (pinfunction "2_2") (pintype "passive"))
      (node (ref "R8") (pin "1") (pinfunction "1_1") (pintype "passive"))
      (node (ref "R9") (pin "1") (pinfunction "1_1") (pintype "passive"))
      (node (ref "SJ1") (pin "2") (pinfunction "2_2") (pintype "passive"))
      (node (ref "SJ2") (pin "2") (pinfunction "2_2") (pintype "passive"))
      (node (ref "SJ3") (pin "2") (pinfunction "2_2") (pintype "passive"))
      (node (ref "U1") (pin "18") (pinfunction "AVCC_18") (pintype "power_in"))
      (node (ref "U1") (pin "20") (pinfunction "AREF_20") (pintype "input"))
      (node (ref "U1") (pin "4") (pinfunction "VCC_4") (pintype "power_in"))
      (node (ref "U2") (pin "VDD") (pinfunction "VDD_VDD") (pintype "power_in"))
      (node (ref "U3") (pin "VDD") (pinfunction "VDD_VDD") (pintype "power_in"))
      (node (ref "U4") (pin "VDD") (pinfunction "VDD_VDD") (pintype "power_in"))
      (node (ref "U5") (pin "16") (pinfunction "VDD_16") (pintype "bidirectional"))
      (node (ref "U7") (pin "2") (pinfunction "VOUT_2") (pintype "power_in"))
      (node (ref "U7") (pin "4") (pinfunction "VOUT_4") (pintype "power_in"))
      (node (ref "U9") (pin "6") (pinfunction "6_6") (pintype "bidirectional"))
    )
    (net (code "80") (name "unconnected-(U2-PadO1)") (class "Default")
      (node (ref "U2") (pin "O1") (pinfunction "O1_O1") (pintype "output"))
    )
    (net (code "81") (name "unconnected-(U3-PadO1)") (class "Default")
      (node (ref "U3") (pin "O1") (pinfunction "O1_O1") (pintype "output"))
    )
    (net (code "82") (name "unconnected-(U4-PadO1)") (class "Default")
      (node (ref "U4") (pin "O1") (pinfunction "O1_O1") (pintype "output"))
    )
  )
)
